# Flight_Controller.net
KiCad netlist of a schematic drawn in Altium Designer
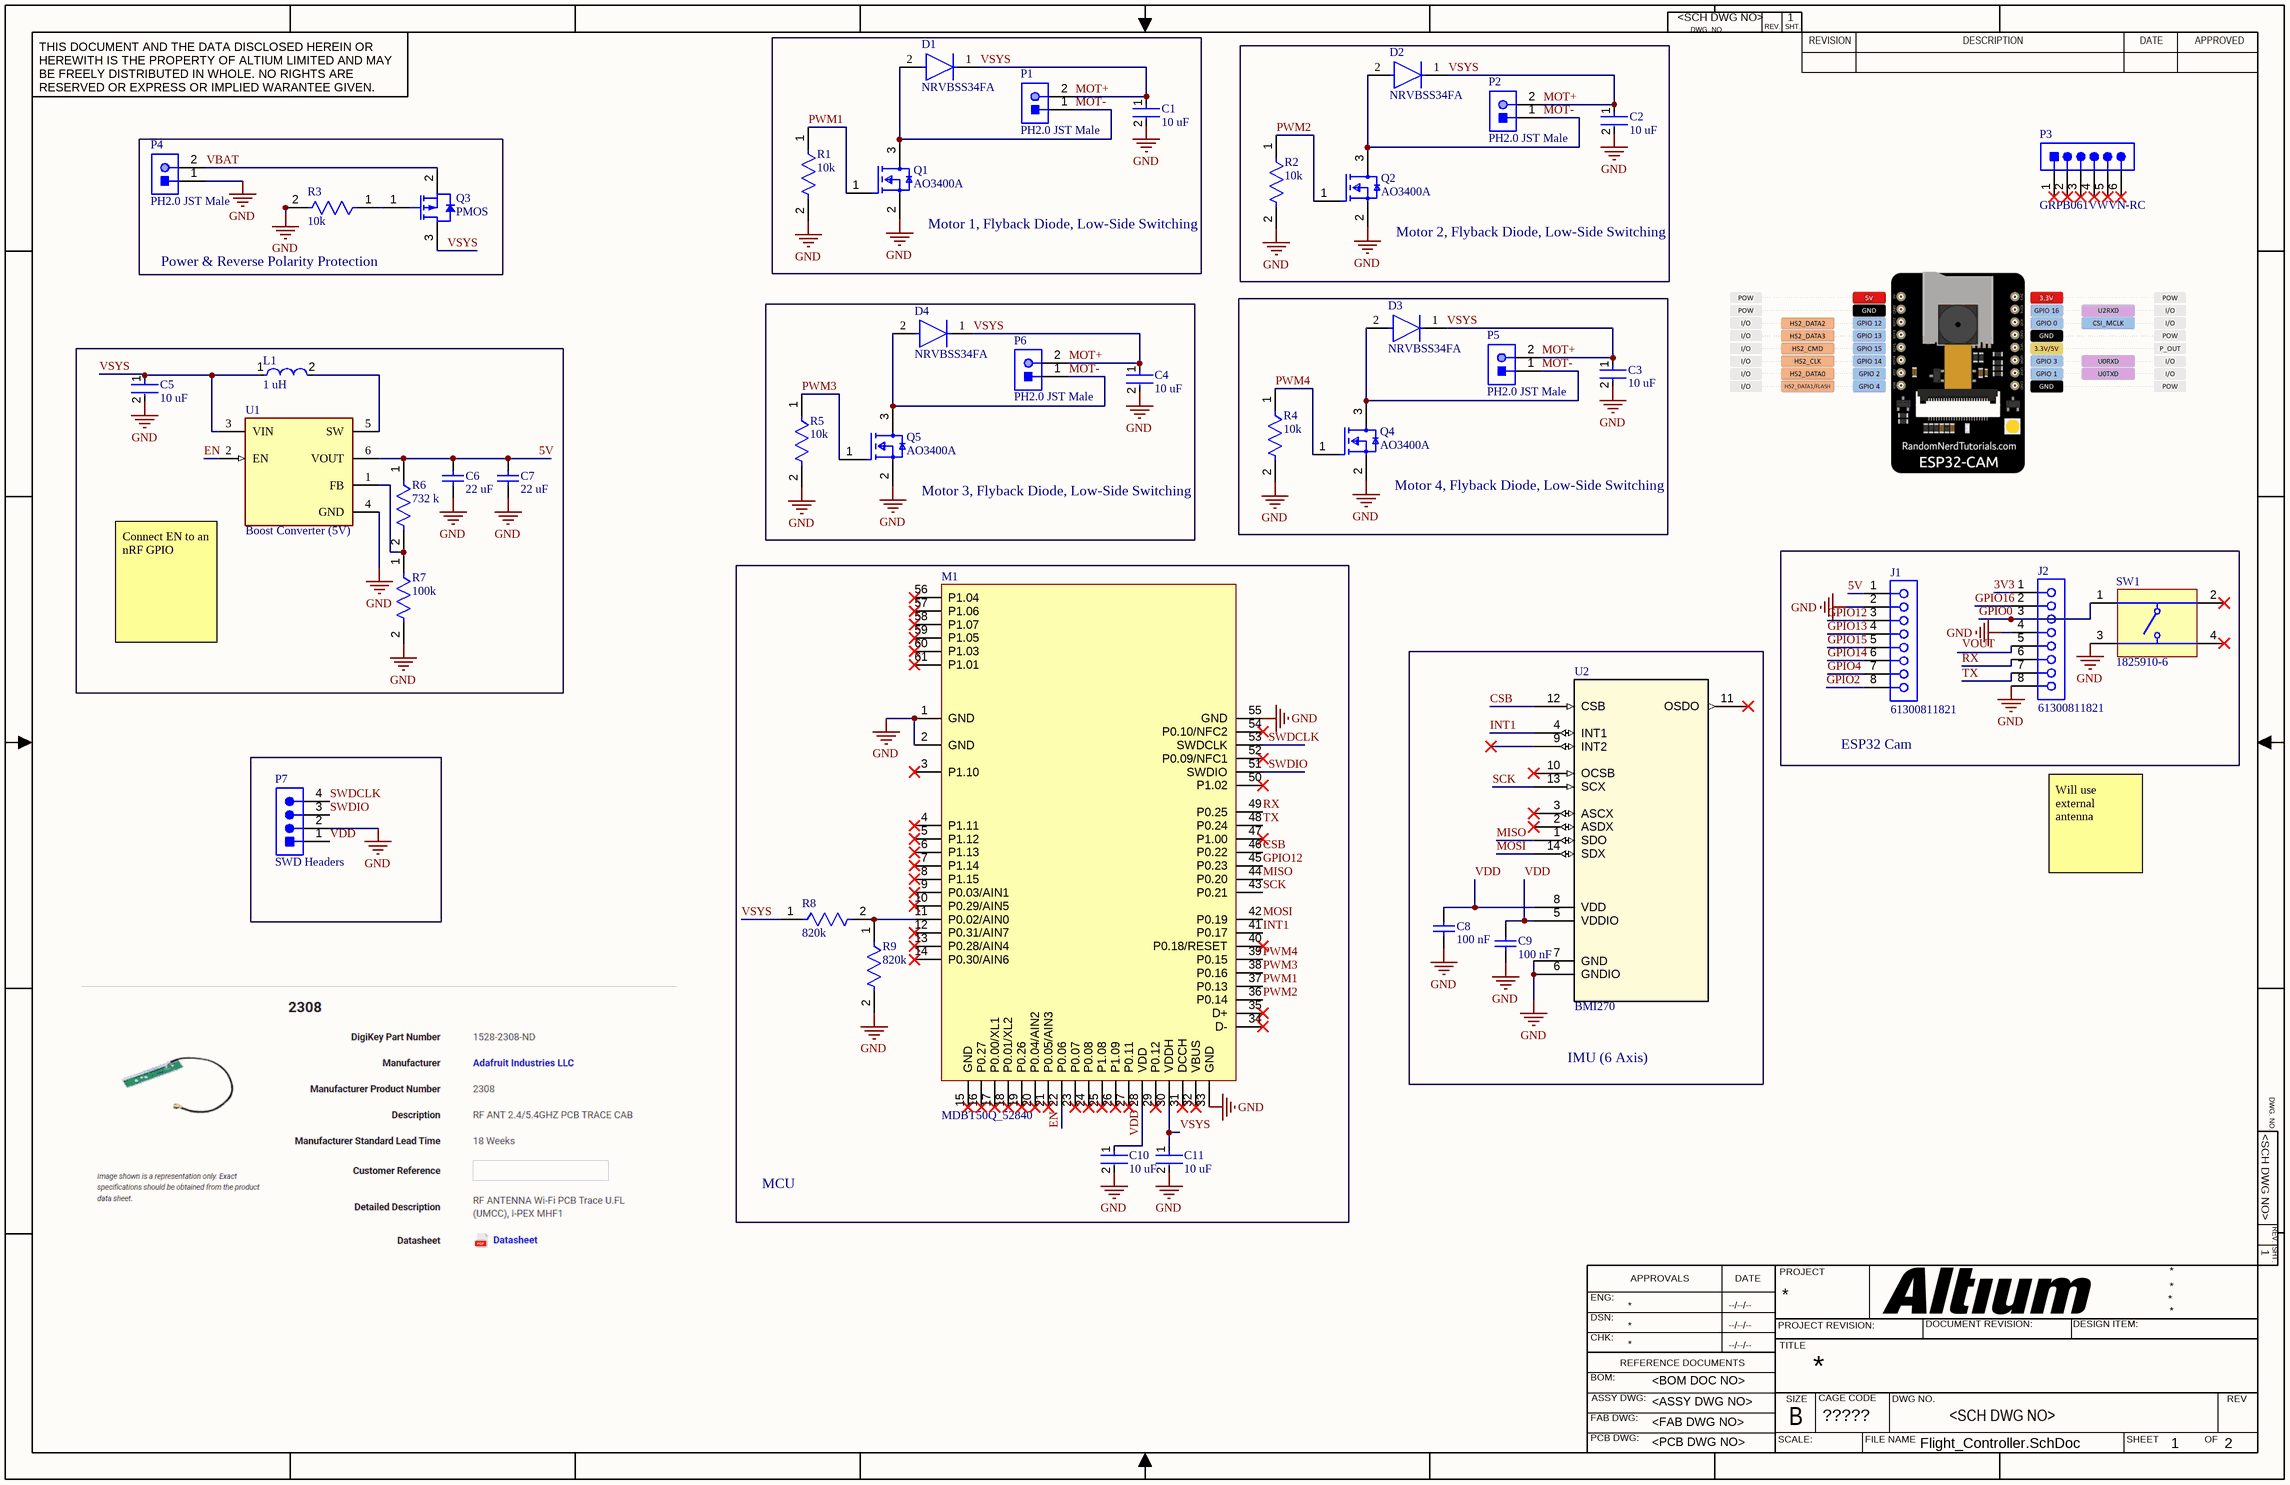
[diagram p0: Flight_Controller.SchDoc]

(export (version "E")
  (design (tool "Eeschema 10.0.6"))
  (components
    (comp (ref "C1")
      (value "10 uF")
      (footprint "FP-1210-L_3_3_0_4-W_2_5_0-IPC_A")
      (description "CAP CER 10UF 10V X7R 1210, 1210ZC106KAT2A")
      (fields (field (name "VOLTAGE") "10V") (field (name "TOLERANCE") "10%"))
      (libsource (lib "Altium Content Vault") (part "b4654b650e69147ec39a6b967a45e02"))
    )
    (comp (ref "C2")
      (value "10 uF")
      (footprint "FP-1210-L_3_3_0_4-W_2_5_0-IPC_A")
      (description "CAP CER 10UF 10V X7R 1210, 1210ZC106KAT2A")
      (fields (field (name "VOLTAGE") "10V") (field (name "TOLERANCE") "10%"))
      (libsource (lib "Altium Content Vault") (part "b4654b650e69147ec39a6b967a45e02"))
    )
    (comp (ref "C3")
      (value "10 uF")
      (footprint "FP-1210-L_3_3_0_4-W_2_5_0-IPC_A")
      (description "CAP CER 10UF 10V X7R 1210, 1210ZC106KAT2A")
      (fields (field (name "VOLTAGE") "10V") (field (name "TOLERANCE") "10%"))
      (libsource (lib "Altium Content Vault") (part "b4654b650e69147ec39a6b967a45e02"))
    )
    (comp (ref "C4")
      (value "10 uF")
      (footprint "FP-1210-L_3_3_0_4-W_2_5_0-IPC_A")
      (description "CAP CER 10UF 10V X7R 1210, 1210ZC106KAT2A")
      (fields (field (name "VOLTAGE") "10V") (field (name "TOLERANCE") "10%"))
      (libsource (lib "Altium Content Vault") (part "b4654b650e69147ec39a6b967a45e02"))
    )
    (comp (ref "C5")
      (value "10 uF")
      (footprint "FP-1210-L_3_3_0_4-W_2_5_0-IPC_A")
      (description "CAP CER 10UF 10V X7R 1210, 1210ZC106KAT2A")
      (fields (field (name "VOLTAGE") "10V") (field (name "TOLERANCE") "10%"))
      (libsource (lib "Altium Content Vault") (part "b4654b650e69147ec39a6b967a45e02"))
    )
    (comp (ref "C6")
      (value "22 uF")
      (footprint "CAPC1608X90X35ML15T15")
      (description "06034D226MAT2A")
      (fields (field (name "MANUFACTURER") "AVX Interconnect / Elco"))
      (libsource (lib "Altium Content Vault") (part "CAP"))
    )
    (comp (ref "C7")
      (value "22 uF")
      (footprint "CAPC1608X90X35ML15T15")
      (description "06034D226MAT2A")
      (fields (field (name "MANUFACTURER") "AVX Interconnect / Elco"))
      (libsource (lib "Altium Content Vault") (part "CAP"))
    )
    (comp (ref "C8")
      (value "100 nF")
      (footprint "CAPC1210(3225)100_L")
      (description "CAP 100nF 16V ±5% 1210 (3225 Metric) Thickness 1mm SMD")
      (fields (field (name "TOLERANCE") "Â±5%"))
      (libsource (lib "Altium Content Vault") (part "CAP"))
    )
    (comp (ref "C9")
      (value "100 nF")
      (footprint "CAPC1210(3225)100_L")
      (description "CAP 100nF 16V ±5% 1210 (3225 Metric) Thickness 1mm SMD")
      (fields (field (name "TOLERANCE") "Â±5%"))
      (libsource (lib "Altium Content Vault") (part "CAP"))
    )
    (comp (ref "C10")
      (value "10 uF")
      (footprint "FP-1210-L_3_3_0_4-W_2_5_0-IPC_A")
      (description "CAP CER 10UF 10V X7R 1210, 1210ZC106KAT2A")
      (fields (field (name "VOLTAGE") "10V") (field (name "TOLERANCE") "10%"))
      (libsource (lib "Altium Content Vault") (part "b4654b650e69147ec39a6b967a45e02"))
    )
    (comp (ref "C11")
      (value "10 uF")
      (footprint "FP-1210-L_3_3_0_4-W_2_5_0-IPC_A")
      (description "CAP CER 10UF 10V X7R 1210, 1210ZC106KAT2A")
      (fields (field (name "VOLTAGE") "10V") (field (name "TOLERANCE") "10%"))
      (libsource (lib "Altium Content Vault") (part "b4654b650e69147ec39a6b967a45e02"))
    )
    (comp (ref "D1")
      (value "NRVBSS34FA")
      (footprint "FP-425AB-MFG")
      (description "NRVBSS34FA Schottky Barrier Rectifier Diode 40V 3A 2-Pin SOD−123FL T/R")
      (libsource (lib "Altium Content Vault") (part "d7152d700b627762746794eb795d46e"))
    )
    (comp (ref "D2")
      (value "NRVBSS34FA")
      (footprint "FP-425AB-MFG")
      (description "NRVBSS34FA Schottky Barrier Rectifier Diode 40V 3A 2-Pin SOD−123FL T/R")
      (libsource (lib "Altium Content Vault") (part "d7152d700b627762746794eb795d46e"))
    )
    (comp (ref "D3")
      (value "NRVBSS34FA")
      (footprint "FP-425AB-MFG")
      (description "NRVBSS34FA Schottky Barrier Rectifier Diode 40V 3A 2-Pin SOD−123FL T/R")
      (libsource (lib "Altium Content Vault") (part "d7152d700b627762746794eb795d46e"))
    )
    (comp (ref "D4")
      (value "NRVBSS34FA")
      (footprint "FP-425AB-MFG")
      (description "NRVBSS34FA Schottky Barrier Rectifier Diode 40V 3A 2-Pin SOD−123FL T/R")
      (libsource (lib "Altium Content Vault") (part "d7152d700b627762746794eb795d46e"))
    )
    (comp (ref "J1")
      (value "61300811821")
      (footprint "61300811821")
      (description "Btb Conn, Rcpt, 8Pos, 1Row, 2.54Mm Rohs Compliant: Yes")
      (libsource (lib "Altium Content Vault") (part "Header_Female_1R_08P"))
    )
    (comp (ref "J2")
      (value "61300811821")
      (footprint "61300811821")
      (description "Btb Conn, Rcpt, 8Pos, 1Row, 2.54Mm Rohs Compliant: Yes")
      (libsource (lib "Altium Content Vault") (part "Header_Female_1R_08P"))
    )
    (comp (ref "L1")
      (value "1 uH")
      (footprint "FP-MLP2016M-IPC_C")
      (description "Shielded Multilayer Inductor 1uH ±20% 1400mA 117mΩ SMD 0806, MLP2016S1R0MT0S1")
      (fields (field (name "TOLERANCE") "20%"))
      (libsource (lib "Altium Content Vault") (part "725321dda6339637d4d059423bc1c3c"))
    )
    (comp (ref "M1")
      (value "MDBT50Q_52840")
      (footprint "MDBT50Q")
      (description "MDBT50Q(52840)")
      (libsource (lib "MDBT50Q_52840_230606") (part "MDBT50Q_52840"))
    )
    (comp (ref "P1")
      (value "PH2.0 JST Male")
      (footprint "JST-S2B-PH-K-S_V")
      (fields (field (name "MANUFACTURER") "Japan Solderless Terminals"))
      (libsource (lib "Altium 365 Cloud") (part "CN-1P-M-R2"))
    )
    (comp (ref "P2")
      (value "PH2.0 JST Male")
      (footprint "JST-S2B-PH-K-S_V")
      (fields (field (name "MANUFACTURER") "Japan Solderless Terminals"))
      (libsource (lib "Altium 365 Cloud") (part "CN-1P-M-R2"))
    )
    (comp (ref "P3")
      (value "GRPB061VWVN-RC")
      (footprint "SLIN-GRPB061VWVN-RC_V")
      (fields (field (name "MANUFACTURER") "Sullins"))
      (libsource (lib "Altium Content Vault") (part "CN-1P-M-R6"))
    )
    (comp (ref "P4")
      (value "PH2.0 JST Male")
      (footprint "JST-S2B-PH-K-S_V")
      (fields (field (name "MANUFACTURER") "Japan Solderless Terminals"))
      (libsource (lib "Altium 365 Cloud") (part "CN-1P-M-R2"))
    )
    (comp (ref "P5")
      (value "PH2.0 JST Male")
      (footprint "JST-S2B-PH-K-S_V")
      (fields (field (name "MANUFACTURER") "Japan Solderless Terminals"))
      (libsource (lib "Altium 365 Cloud") (part "CN-1P-M-R2"))
    )
    (comp (ref "P6")
      (value "PH2.0 JST Male")
      (footprint "JST-S2B-PH-K-S_V")
      (fields (field (name "MANUFACTURER") "Japan Solderless Terminals"))
      (libsource (lib "Altium 365 Cloud") (part "CN-1P-M-R2"))
    )
    (comp (ref "P7")
      (value "SWD Headers")
      (footprint "SLIN-GRPB041VWVN-RC_V")
      (fields (field (name "MANUFACTURER") "Sullins"))
      (libsource (lib "Altium Content Vault") (part "CN-1P-M-R4"))
    )
    (comp (ref "Q1")
      (value "AO3400A")
      (footprint "FP-SOT23-MFG")
      (description "MOSFET N-CH 30V 5.7A SOT23")
      (libsource (lib "Altium Content Vault") (part "0a9ea7c96deaaede766a5b531c28de0"))
    )
    (comp (ref "Q2")
      (value "AO3400A")
      (footprint "FP-SOT23-MFG")
      (description "MOSFET N-CH 30V 5.7A SOT23")
      (libsource (lib "Altium Content Vault") (part "0a9ea7c96deaaede766a5b531c28de0"))
    )
    (comp (ref "Q3")
      (value "PMOS")
      (footprint "AO-SOT-23-3L_V")
      (description "P-Channel MOSFET, 30 V, 4 A, -55 to 150 degC, 3-Pin SOT-23-3L, RoHS, Tape and Reel, AO3401A")
      (fields (field (name "MANUFACTURER") "Alpha and Omega"))
      (libsource (lib "Altium Content Vault") (part "PEMOS-GSD-3"))
    )
    (comp (ref "Q4")
      (value "AO3400A")
      (footprint "FP-SOT23-MFG")
      (description "MOSFET N-CH 30V 5.7A SOT23")
      (libsource (lib "Altium Content Vault") (part "0a9ea7c96deaaede766a5b531c28de0"))
    )
    (comp (ref "Q5")
      (value "AO3400A")
      (footprint "FP-SOT23-MFG")
      (description "MOSFET N-CH 30V 5.7A SOT23")
      (libsource (lib "Altium Content Vault") (part "0a9ea7c96deaaede766a5b531c28de0"))
    )
    (comp (ref "R1")
      (value "10k")
      (footprint "FP-CRGCQ1210-IPC_C")
      (description "CRGCQ1210 10KΩ 0.5W ±100ppm/°C 5% 200V")
      (fields (field (name "TOLERANCE") "0.05") (field (name "MANUFACTURER PART NUMBER") "CRGCQ1210J10K"))
      (libsource (lib "Altium Content Vault") (part "1029c3af85768c4190bb7ad29bc67b5"))
    )
    (comp (ref "R2")
      (value "10k")
      (footprint "FP-CRGCQ1210-IPC_C")
      (description "CRGCQ1210 10KΩ 0.5W ±100ppm/°C 5% 200V")
      (fields (field (name "TOLERANCE") "0.05") (field (name "MANUFACTURER PART NUMBER") "CRGCQ1210J10K"))
      (libsource (lib "Altium Content Vault") (part "1029c3af85768c4190bb7ad29bc67b5"))
    )
    (comp (ref "R3")
      (value "10k")
      (footprint "FP-CRGCQ1210-IPC_C")
      (description "CRGCQ1210 10KΩ 0.5W ±100ppm/°C 5% 200V")
      (fields (field (name "TOLERANCE") "0.05") (field (name "MANUFACTURER PART NUMBER") "CRGCQ1210J10K"))
      (libsource (lib "Altium Content Vault") (part "1029c3af85768c4190bb7ad29bc67b5"))
    )
    (comp (ref "R4")
      (value "10k")
      (footprint "FP-CRGCQ1210-IPC_C")
      (description "CRGCQ1210 10KΩ 0.5W ±100ppm/°C 5% 200V")
      (fields (field (name "TOLERANCE") "0.05") (field (name "MANUFACTURER PART NUMBER") "CRGCQ1210J10K"))
      (libsource (lib "Altium Content Vault") (part "1029c3af85768c4190bb7ad29bc67b5"))
    )
    (comp (ref "R5")
      (value "10k")
      (footprint "FP-CRGCQ1210-IPC_C")
      (description "CRGCQ1210 10KΩ 0.5W ±100ppm/°C 5% 200V")
      (fields (field (name "TOLERANCE") "0.05") (field (name "MANUFACTURER PART NUMBER") "CRGCQ1210J10K"))
      (libsource (lib "Altium Content Vault") (part "1029c3af85768c4190bb7ad29bc67b5"))
    )
    (comp (ref "R6")
      (value "732 k")
      (footprint "FP-AC0603-IPC_B")
      (description "RES 732KΩ 1.00% 0.1W 0603, AC0603FR-07732KL")
      (fields (field (name "TOLERANCE") "1%"))
      (libsource (lib "Altium Content Vault") (part "1029c3af85768c4190bb7ad29bc67b5"))
    )
    (comp (ref "R7")
      (value "100k")
      (footprint "FP-AC1210-MFG")
      (description "RES SMD 100K OHM 5% 1/2W 1210, AC1210JR-07100KL")
      (fields
        (field (name "MANUFACTURER") "Yageo")
        (field (name "MANUFACTURER PART NUMBER") "AC1210JR-07100KL")
      )
      (libsource (lib "Altium Content Vault") (part "1029c3af85768c4190bb7ad29bc67b5"))
    )
    (comp (ref "R8")
      (value "820k")
      (footprint "FP-AC1206-MFG")
      (description "RES SMD 820K OHM 1% 1/4W 1206, AC1206FR-07820KL")
      (fields
        (field (name "TOLERANCE") "0.01")
        (field (name "OCTOPART") "https://octopart.com/ac1206fr-07820kl-yageo-71368214")
      )
      (libsource (lib "Altium Content Vault") (part "1029c3af85768c4190bb7ad29bc67b5"))
    )
    (comp (ref "R9")
      (value "820k")
      (footprint "FP-AC1206-MFG")
      (description "RES SMD 820K OHM 1% 1/4W 1206, AC1206FR-07820KL")
      (fields
        (field (name "TOLERANCE") "0.01")
        (field (name "OCTOPART") "https://octopart.com/ac1206fr-07820kl-yageo-71368214")
      )
      (libsource (lib "Altium Content Vault") (part "1029c3af85768c4190bb7ad29bc67b5"))
    )
    (comp (ref "SW1")
      (value "1825910-6")
      (footprint "TECO-1825910-6_V")
      (description "Tact Switch, SPST-NO, 0.05 A, -35 to 85 degC, 4-Pin THD, RoHS, Bulk")
      (fields (field (name "MANUFACTURER") "TE Connectivity"))
      (libsource (lib "Altium Content Vault") (part "SW-SPST-4_A"))
    )
    (comp (ref "U1")
      (value "Boost Converter (5V)")
      (footprint "FP-DRL0006A-MFG")
      (description "FINISH GOODS FOR TPS61023,TPS61023DRLR")
      (libsource (lib "Altium Content Vault") (part "b28b3e956a4ad07201ce69f9d09f9a8"))
    )
    (comp (ref "U2")
      (value "BMI270")
      (footprint "BMI270_BOS")
      (description "Description")
      (fields (field (name "COPYRIGHT") "Copyright (C) 2025 Ultra Librarian. All rights reserved."))
      (libsource (lib "BMI270") (part "BMI270"))
    )
  )
  (nets
    (net (code "1") (name "/3V3") (class "Default")
      (node (ref "J2") (pin "1") (pinfunction "1_1") (pintype "passive"))
    )
    (net (code "2") (name "/5V") (class "Default")
      (node (ref "C6") (pin "1") (pinfunction "1_1") (pintype "passive"))
      (node (ref "C7") (pin "1") (pinfunction "1_1") (pintype "passive"))
      (node (ref "J1") (pin "1") (pinfunction "1_1") (pintype "passive"))
      (node (ref "R6") (pin "1") (pinfunction "1_1") (pintype "passive"))
      (node (ref "U1") (pin "6") (pinfunction "VOUT_6") (pintype "power_in"))
    )
    (net (code "3") (name "/CSB") (class "Default")
      (node (ref "M1") (pin "46") (pinfunction "P0.22_46") (pintype "passive"))
      (node (ref "U2") (pin "12") (pinfunction "CSB_12") (pintype "input"))
    )
    (net (code "4") (name "/EN") (class "Default")
      (node (ref "M1") (pin "22") (pinfunction "P0.06_22") (pintype "passive"))
      (node (ref "U1") (pin "2") (pinfunction "EN_2") (pintype "input"))
    )
    (net (code "5") (name "/GPIO0") (class "Default")
      (node (ref "J2") (pin "3") (pinfunction "3_3") (pintype "passive"))
      (node (ref "SW1") (pin "1") (pinfunction "1_1") (pintype "passive"))
    )
    (net (code "6") (name "/GPIO2") (class "Default")
      (node (ref "J1") (pin "8") (pinfunction "8_8") (pintype "passive"))
    )
    (net (code "7") (name "/GPIO4") (class "Default")
      (node (ref "J1") (pin "7") (pinfunction "7_7") (pintype "passive"))
    )
    (net (code "8") (name "/GPIO12") (class "Default")
      (node (ref "J1") (pin "3") (pinfunction "3_3") (pintype "passive"))
      (node (ref "M1") (pin "45") (pinfunction "P0.23_45") (pintype "passive"))
    )
    (net (code "9") (name "/GPIO13") (class "Default")
      (node (ref "J1") (pin "4") (pinfunction "4_4") (pintype "passive"))
    )
    (net (code "10") (name "/GPIO14") (class "Default")
      (node (ref "J1") (pin "6") (pinfunction "6_6") (pintype "passive"))
    )
    (net (code "11") (name "/GPIO15") (class "Default")
      (node (ref "J1") (pin "5") (pinfunction "5_5") (pintype "passive"))
    )
    (net (code "12") (name "/GPIO16") (class "Default")
      (node (ref "J2") (pin "2") (pinfunction "2_2") (pintype "passive"))
    )
    (net (code "13") (name "/INT1") (class "Default")
      (node (ref "M1") (pin "41") (pinfunction "P0.17_41") (pintype "passive"))
      (node (ref "U2") (pin "4") (pinfunction "INT1_4") (pintype "bidirectional"))
    )
    (net (code "14") (name "/MISO") (class "Default")
      (node (ref "M1") (pin "44") (pinfunction "P0.20_44") (pintype "passive"))
      (node (ref "U2") (pin "1") (pinfunction "SDO_1") (pintype "bidirectional"))
    )
    (net (code "15") (name "/MOSI") (class "Default")
      (node (ref "M1") (pin "42") (pinfunction "P0.19_42") (pintype "passive"))
      (node (ref "U2") (pin "14") (pinfunction "SDX_14") (pintype "bidirectional"))
    )
    (net (code "16") (name "/MOT+") (class "Default")
      (node (ref "C1") (pin "1") (pinfunction "1_1") (pintype "passive"))
      (node (ref "C11") (pin "1") (pinfunction "1_1") (pintype "passive"))
      (node (ref "C2") (pin "1") (pinfunction "1_1") (pintype "passive"))
      (node (ref "C3") (pin "1") (pinfunction "1_1") (pintype "passive"))
      (node (ref "C4") (pin "1") (pinfunction "1_1") (pintype "passive"))
      (node (ref "C5") (pin "1") (pinfunction "1_1") (pintype "passive"))
      (node (ref "D1") (pin "1") (pinfunction "C_1") (pintype "passive"))
      (node (ref "D2") (pin "1") (pinfunction "C_1") (pintype "passive"))
      (node (ref "D3") (pin "1") (pinfunction "C_1") (pintype "passive"))
      (node (ref "D4") (pin "1") (pinfunction "C_1") (pintype "passive"))
      (node (ref "L1") (pin "1") (pinfunction "1_1") (pintype "passive"))
      (node (ref "M1") (pin "30") (pinfunction "VDDH_30") (pintype "passive"))
      (node (ref "P1") (pin "2") (pinfunction "2_2") (pintype "passive"))
      (node (ref "P2") (pin "2") (pinfunction "2_2") (pintype "passive"))
      (node (ref "P5") (pin "2") (pinfunction "2_2") (pintype "passive"))
      (node (ref "P6") (pin "2") (pinfunction "2_2") (pintype "passive"))
      (node (ref "Q3") (pin "3") (pinfunction "DRAIN_3") (pintype "passive"))
      (node (ref "R8") (pin "1") (pinfunction "1_1") (pintype "passive"))
      (node (ref "U1") (pin "3") (pinfunction "VIN_3") (pintype "power_in"))
    )
    (net (code "17") (name "/MOT-") (class "Default")
      (node (ref "D1") (pin "2") (pinfunction "A_2") (pintype "passive"))
      (node (ref "D2") (pin "2") (pinfunction "A_2") (pintype "passive"))
      (node (ref "D3") (pin "2") (pinfunction "A_2") (pintype "passive"))
      (node (ref "D4") (pin "2") (pinfunction "A_2") (pintype "passive"))
      (node (ref "P1") (pin "1") (pinfunction "1_1") (pintype "passive"))
      (node (ref "P2") (pin "1") (pinfunction "1_1") (pintype "passive"))
      (node (ref "P5") (pin "1") (pinfunction "1_1") (pintype "passive"))
      (node (ref "P6") (pin "1") (pinfunction "1_1") (pintype "passive"))
      (node (ref "Q1") (pin "3") (pinfunction "D_3") (pintype "passive"))
      (node (ref "Q2") (pin "3") (pinfunction "D_3") (pintype "passive"))
      (node (ref "Q4") (pin "3") (pinfunction "D_3") (pintype "passive"))
      (node (ref "Q5") (pin "3") (pinfunction "D_3") (pintype "passive"))
    )
    (net (code "18") (name "/PWM1") (class "Default")
      (node (ref "M1") (pin "37") (pinfunction "P0.13_37") (pintype "passive"))
      (node (ref "Q1") (pin "1") (pinfunction "G_1") (pintype "passive"))
      (node (ref "R1") (pin "1") (pinfunction "1_1") (pintype "passive"))
    )
    (net (code "19") (name "/PWM2") (class "Default")
      (node (ref "M1") (pin "36") (pinfunction "P0.14_36") (pintype "passive"))
      (node (ref "Q2") (pin "1") (pinfunction "G_1") (pintype "passive"))
      (node (ref "R2") (pin "1") (pinfunction "1_1") (pintype "passive"))
    )
    (net (code "20") (name "/PWM3") (class "Default")
      (node (ref "M1") (pin "38") (pinfunction "P0.16_38") (pintype "passive"))
      (node (ref "Q5") (pin "1") (pinfunction "G_1") (pintype "passive"))
      (node (ref "R5") (pin "1") (pinfunction "1_1") (pintype "passive"))
    )
    (net (code "21") (name "/PWM4") (class "Default")
      (node (ref "M1") (pin "39") (pinfunction "P0.15_39") (pintype "passive"))
      (node (ref "Q4") (pin "1") (pinfunction "G_1") (pintype "passive"))
      (node (ref "R4") (pin "1") (pinfunction "1_1") (pintype "passive"))
    )
    (net (code "22") (name "/RX") (class "Default")
      (node (ref "J2") (pin "6") (pinfunction "6_6") (pintype "passive"))
      (node (ref "M1") (pin "49") (pinfunction "P0.25_49") (pintype "passive"))
    )
    (net (code "23") (name "/SCK") (class "Default")
      (node (ref "M1") (pin "43") (pinfunction "P0.21_43") (pintype "passive"))
      (node (ref "U2") (pin "13") (pinfunction "SCX_13") (pintype "input"))
    )
    (net (code "24") (name "/SWDCLK") (class "Default")
      (node (ref "M1") (pin "53") (pinfunction "SWDCLK_53") (pintype "passive"))
      (node (ref "P7") (pin "4") (pinfunction "4_4") (pintype "passive"))
    )
    (net (code "25") (name "/SWDIO") (class "Default")
      (node (ref "M1") (pin "51") (pinfunction "SWDIO_51") (pintype "passive"))
      (node (ref "P7") (pin "3") (pinfunction "3_3") (pintype "passive"))
    )
    (net (code "26") (name "/TX") (class "Default")
      (node (ref "J2") (pin "7") (pinfunction "7_7") (pintype "passive"))
      (node (ref "M1") (pin "48") (pinfunction "P0.24_48") (pintype "passive"))
    )
    (net (code "27") (name "/VBAT") (class "Default")
      (node (ref "P4") (pin "2") (pinfunction "2_2") (pintype "passive"))
      (node (ref "Q3") (pin "2") (pinfunction "SOURCE_2") (pintype "passive"))
    )
    (net (code "28") (name "/VDD") (class "Default")
      (node (ref "C10") (pin "1") (pinfunction "1_1") (pintype "passive"))
      (node (ref "C8") (pin "2") (pinfunction "2_2") (pintype "passive"))
      (node (ref "C9") (pin "2") (pinfunction "2_2") (pintype "passive"))
      (node (ref "M1") (pin "28") (pinfunction "VDD_28") (pintype "passive"))
      (node (ref "P7") (pin "1") (pinfunction "1_1") (pintype "passive"))
      (node (ref "U2") (pin "5") (pinfunction "VDDIO_5") (pintype "power_in"))
      (node (ref "U2") (pin "8") (pinfunction "VDD_8") (pintype "power_in"))
    )
    (net (code "30") (name "GND") (class "Default")
      (node (ref "C1") (pin "2") (pinfunction "2_2") (pintype "passive"))
      (node (ref "C10") (pin "2") (pinfunction "2_2") (pintype "passive"))
      (node (ref "C11") (pin "2") (pinfunction "2_2") (pintype "passive"))
      (node (ref "C2") (pin "2") (pinfunction "2_2") (pintype "passive"))
      (node (ref "C3") (pin "2") (pinfunction "2_2") (pintype "passive"))
      (node (ref "C4") (pin "2") (pinfunction "2_2") (pintype "passive"))
      (node (ref "C5") (pin "2") (pinfunction "2_2") (pintype "passive"))
      (node (ref "C6") (pin "2") (pinfunction "2_2") (pintype "passive"))
      (node (ref "C7") (pin "2") (pinfunction "2_2") (pintype "passive"))
      (node (ref "C8") (pin "1") (pinfunction "1_1") (pintype "passive"))
      (node (ref "C9") (pin "1") (pinfunction "1_1") (pintype "passive"))
      (node (ref "J1") (pin "2") (pinfunction "2_2") (pintype "passive"))
      (node (ref "J2") (pin "4") (pinfunction "4_4") (pintype "passive"))
      (node (ref "J2") (pin "8") (pinfunction "8_8") (pintype "passive"))
      (node (ref "M1") (pin "1") (pinfunction "GND_1") (pintype "passive"))
      (node (ref "M1") (pin "2") (pinfunction "GND_2") (pintype "passive"))
      (node (ref "M1") (pin "33") (pinfunction "GND_33") (pintype "passive"))
      (node (ref "M1") (pin "55") (pinfunction "GND_55") (pintype "passive"))
      (node (ref "P4") (pin "1") (pinfunction "1_1") (pintype "passive"))
      (node (ref "P7") (pin "2") (pinfunction "2_2") (pintype "passive"))
      (node (ref "Q1") (pin "2") (pinfunction "S_2") (pintype "passive"))
      (node (ref "Q2") (pin "2") (pinfunction "S_2") (pintype "passive"))
      (node (ref "Q4") (pin "2") (pinfunction "S_2") (pintype "passive"))
      (node (ref "Q5") (pin "2") (pinfunction "S_2") (pintype "passive"))
      (node (ref "R1") (pin "2") (pinfunction "2_2") (pintype "passive"))
      (node (ref "R2") (pin "2") (pinfunction "2_2") (pintype "passive"))
      (node (ref "R3") (pin "2") (pinfunction "2_2") (pintype "passive"))
      (node (ref "R4") (pin "2") (pinfunction "2_2") (pintype "passive"))
      (node (ref "R5") (pin "2") (pinfunction "2_2") (pintype "passive"))
      (node (ref "R7") (pin "2") (pinfunction "2_2") (pintype "passive"))
      (node (ref "R9") (pin "2") (pinfunction "2_2") (pintype "passive"))
      (node (ref "SW1") (pin "3") (pinfunction "3_3") (pintype "passive"))
      (node (ref "U1") (pin "4") (pinfunction "GND_4") (pintype "power_in"))
      (node (ref "U2") (pin "6") (pinfunction "GNDIO_6") (pintype "power_in"))
      (node (ref "U2") (pin "7") (pinfunction "GND_7") (pintype "power_in"))
    )
    (net (code "31") (name "Net-(M1-P0.02{slash}AIN0)") (class "Default")
      (node (ref "M1") (pin "11") (pinfunction "P0.02/AIN0_11") (pintype "passive"))
      (node (ref "R8") (pin "2") (pinfunction "2_2") (pintype "passive"))
      (node (ref "R9") (pin "1") (pinfunction "1_1") (pintype "passive"))
    )
    (net (code "32") (name "Net-(Q3-GATE)") (class "Default")
      (node (ref "Q3") (pin "1") (pinfunction "GATE_1") (pintype "passive"))
      (node (ref "R3") (pin "1") (pinfunction "1_1") (pintype "passive"))
    )
    (net (code "33") (name "Net-(U1-FB)") (class "Default")
      (node (ref "R6") (pin "2") (pinfunction "2_2") (pintype "passive"))
      (node (ref "R7") (pin "1") (pinfunction "1_1") (pintype "passive"))
      (node (ref "U1") (pin "1") (pinfunction "FB_1") (pintype "passive"))
    )
    (net (code "34") (name "Net-(U1-SW)") (class "Default")
      (node (ref "L1") (pin "2") (pinfunction "2_2") (pintype "passive"))
      (node (ref "U1") (pin "5") (pinfunction "SW_5") (pintype "passive"))
    )
    (net (code "35") (name "unconnected-(J2-Pad5)") (class "Default")
      (node (ref "J2") (pin "5") (pinfunction "5_5") (pintype "passive"))
    )
    (net (code "36") (name "unconnected-(M1-D+-Pad35)") (class "Default")
      (node (ref "M1") (pin "35") (pinfunction "D+_35") (pintype "passive+no_connect"))
    )
    (net (code "37") (name "unconnected-(M1-D--Pad34)") (class "Default")
      (node (ref "M1") (pin "34") (pinfunction "D-_34") (pintype "passive+no_connect"))
    )
    (net (code "38") (name "unconnected-(M1-DCCH-Pad31)") (class "Default")
      (node (ref "M1") (pin "31") (pinfunction "DCCH_31") (pintype "passive+no_connect"))
    )
    (net (code "39") (name "unconnected-(M1-GND-Pad15)") (class "Default")
      (node (ref "M1") (pin "15") (pinfunction "GND_15") (pintype "passive+no_connect"))
    )
    (net (code "40") (name "unconnected-(M1-P0.00{slash}XL1-Pad17)") (class "Default")
      (node (ref "M1") (pin "17") (pinfunction "P0.00/XL1_17") (pintype "passive+no_connect"))
    )
    (net (code "41") (name "unconnected-(M1-P0.01{slash}XL2-Pad18)") (class "Default")
      (node (ref "M1") (pin "18") (pinfunction "P0.01/XL2_18") (pintype "passive+no_connect"))
    )
    (net (code "42") (name "unconnected-(M1-P0.03{slash}AIN1-Pad9)") (class "Default")
      (node (ref "M1") (pin "9") (pinfunction "P0.03/AIN1_9") (pintype "passive+no_connect"))
    )
    (net (code "43") (name "unconnected-(M1-P0.04{slash}AIN2-Pad20)") (class "Default")
      (node (ref "M1") (pin "20") (pinfunction "P0.04/AIN2_20") (pintype "passive+no_connect"))
    )
    (net (code "44") (name "unconnected-(M1-P0.05{slash}AIN3-Pad21)") (class "Default")
      (node (ref "M1") (pin "21") (pinfunction "P0.05/AIN3_21") (pintype "passive+no_connect"))
    )
    (net (code "45") (name "unconnected-(M1-P0.07-Pad23)") (class "Default")
      (node (ref "M1") (pin "23") (pinfunction "P0.07_23") (pintype "passive+no_connect"))
    )
    (net (code "46") (name "unconnected-(M1-P0.08-Pad24)") (class "Default")
      (node (ref "M1") (pin "24") (pinfunction "P0.08_24") (pintype "passive+no_connect"))
    )
    (net (code "47") (name "unconnected-(M1-P0.09{slash}NFC1-Pad52)") (class "Default")
      (node (ref "M1") (pin "52") (pinfunction "P0.09/NFC1_52") (pintype "passive+no_connect"))
    )
    (net (code "48") (name "unconnected-(M1-P0.10{slash}NFC2-Pad54)") (class "Default")
      (node (ref "M1") (pin "54") (pinfunction "P0.10/NFC2_54") (pintype "passive+no_connect"))
    )
    (net (code "49") (name "unconnected-(M1-P0.11-Pad27)") (class "Default")
      (node (ref "M1") (pin "27") (pinfunction "P0.11_27") (pintype "passive+no_connect"))
    )
    (net (code "50") (name "unconnected-(M1-P0.12-Pad29)") (class "Default")
      (node (ref "M1") (pin "29") (pinfunction "P0.12_29") (pintype "passive+no_connect"))
    )
    (net (code "51") (name "unconnected-(M1-P0.18{slash}RESET-Pad40)") (class "Default")
      (node (ref "M1") (pin "40") (pinfunction "P0.18/RESET_40") (pintype "passive+no_connect"))
    )
    (net (code "52") (name "unconnected-(M1-P0.26-Pad19)") (class "Default")
      (node (ref "M1") (pin "19") (pinfunction "P0.26_19") (pintype "passive+no_connect"))
    )
    (net (code "53") (name "unconnected-(M1-P0.27-Pad16)") (class "Default")
      (node (ref "M1") (pin "16") (pinfunction "P0.27_16") (pintype "passive+no_connect"))
    )
    (net (code "54") (name "unconnected-(M1-P0.28{slash}AIN4-Pad13)") (class "Default")
      (node (ref "M1") (pin "13") (pinfunction "P0.28/AIN4_13") (pintype "passive+no_connect"))
    )
    (net (code "55") (name "unconnected-(M1-P0.29{slash}AIN5-Pad10)") (class "Default")
      (node (ref "M1") (pin "10") (pinfunction "P0.29/AIN5_10") (pintype "passive+no_connect"))
    )
    (net (code "56") (name "unconnected-(M1-P0.30{slash}AIN6-Pad14)") (class "Default")
      (node (ref "M1") (pin "14") (pinfunction "P0.30/AIN6_14") (pintype "passive+no_connect"))
    )
    (net (code "57") (name "unconnected-(M1-P0.31{slash}AIN7-Pad12)") (class "Default")
      (node (ref "M1") (pin "12") (pinfunction "P0.31/AIN7_12") (pintype "passive+no_connect"))
    )
    (net (code "58") (name "unconnected-(M1-P1.00-Pad47)") (class "Default")
      (node (ref "M1") (pin "47") (pinfunction "P1.00_47") (pintype "passive+no_connect"))
    )
    (net (code "59") (name "unconnected-(M1-P1.01-Pad61)") (class "Default")
      (node (ref "M1") (pin "61") (pinfunction "P1.01_61") (pintype "passive+no_connect"))
    )
    (net (code "60") (name "unconnected-(M1-P1.02-Pad50)") (class "Default")
      (node (ref "M1") (pin "50") (pinfunction "P1.02_50") (pintype "passive+no_connect"))
    )
    (net (code "61") (name "unconnected-(M1-P1.03-Pad60)") (class "Default")
      (node (ref "M1") (pin "60") (pinfunction "P1.03_60") (pintype "passive+no_connect"))
    )
    (net (code "62") (name "unconnected-(M1-P1.04-Pad56)") (class "Default")
      (node (ref "M1") (pin "56") (pinfunction "P1.04_56") (pintype "passive+no_connect"))
    )
    (net (code "63") (name "unconnected-(M1-P1.05-Pad59)") (class "Default")
      (node (ref "M1") (pin "59") (pinfunction "P1.05_59") (pintype "passive+no_connect"))
    )
    (net (code "64") (name "unconnected-(M1-P1.06-Pad57)") (class "Default")
      (node (ref "M1") (pin "57") (pinfunction "P1.06_57") (pintype "passive+no_connect"))
    )
    (net (code "65") (name "unconnected-(M1-P1.07-Pad58)") (class "Default")
      (node (ref "M1") (pin "58") (pinfunction "P1.07_58") (pintype "passive+no_connect"))
    )
    (net (code "66") (name "unconnected-(M1-P1.08-Pad25)") (class "Default")
      (node (ref "M1") (pin "25") (pinfunction "P1.08_25") (pintype "passive+no_connect"))
    )
    (net (code "67") (name "unconnected-(M1-P1.09-Pad26)") (class "Default")
      (node (ref "M1") (pin "26") (pinfunction "P1.09_26") (pintype "passive+no_connect"))
    )
    (net (code "68") (name "unconnected-(M1-P1.10-Pad3)") (class "Default")
      (node (ref "M1") (pin "3") (pinfunction "P1.10_3") (pintype "passive+no_connect"))
    )
    (net (code "69") (name "unconnected-(M1-P1.11-Pad4)") (class "Default")
      (node (ref "M1") (pin "4") (pinfunction "P1.11_4") (pintype "passive+no_connect"))
    )
    (net (code "70") (name "unconnected-(M1-P1.12-Pad5)") (class "Default")
      (node (ref "M1") (pin "5") (pinfunction "P1.12_5") (pintype "passive+no_connect"))
    )
    (net (code "71") (name "unconnected-(M1-P1.13-Pad6)") (class "Default")
      (node (ref "M1") (pin "6") (pinfunction "P1.13_6") (pintype "passive+no_connect"))
    )
    (net (code "72") (name "unconnected-(M1-P1.14-Pad7)") (class "Default")
      (node (ref "M1") (pin "7") (pinfunction "P1.14_7") (pintype "passive+no_connect"))
    )
    (net (code "73") (name "unconnected-(M1-P1.15-Pad8)") (class "Default")
      (node (ref "M1") (pin "8") (pinfunction "P1.15_8") (pintype "passive+no_connect"))
    )
    (net (code "74") (name "unconnected-(M1-VBUS-Pad32)") (class "Default")
      (node (ref "M1") (pin "32") (pinfunction "VBUS_32") (pintype "passive+no_connect"))
    )
    (net (code "75") (name "unconnected-(P3-Pad1)") (class "Default")
      (node (ref "P3") (pin "1") (pinfunction "1_1") (pintype "passive+no_connect"))
    )
    (net (code "76") (name "unconnected-(P3-Pad2)") (class "Default")
      (node (ref "P3") (pin "2") (pinfunction "2_2") (pintype "passive+no_connect"))
    )
    (net (code "77") (name "unconnected-(P3-Pad3)") (class "Default")
      (node (ref "P3") (pin "3") (pinfunction "3_3") (pintype "passive+no_connect"))
    )
    (net (code "78") (name "unconnected-(P3-Pad4)") (class "Default")
      (node (ref "P3") (pin "4") (pinfunction "4_4") (pintype "passive+no_connect"))
    )
    (net (code "79") (name "unconnected-(P3-Pad5)") (class "Default")
      (node (ref "P3") (pin "5") (pinfunction "5_5") (pintype "passive+no_connect"))
    )
    (net (code "80") (name "unconnected-(P3-Pad6)") (class "Default")
      (node (ref "P3") (pin "6") (pinfunction "6_6") (pintype "passive+no_connect"))
    )
    (net (code "81") (name "unconnected-(SW1-Pad2)") (class "Default")
      (node (ref "SW1") (pin "2") (pinfunction "2_2") (pintype "passive+no_connect"))
    )
    (net (code "82") (name "unconnected-(SW1-Pad4)") (class "Default")
      (node (ref "SW1") (pin "4") (pinfunction "4_4") (pintype "passive+no_connect"))
    )
    (net (code "83") (name "unconnected-(U2-ASCX-Pad3)") (class "Default")
      (node (ref "U2") (pin "3") (pinfunction "ASCX_3") (pintype "bidirectional+no_connect"))
    )
    (net (code "84") (name "unconnected-(U2-ASDX-Pad2)") (class "Default")
      (node (ref "U2") (pin "2") (pinfunction "ASDX_2") (pintype "bidirectional+no_connect"))
    )
    (net (code "85") (name "unconnected-(U2-INT2-Pad9)") (class "Default")
      (node (ref "U2") (pin "9") (pinfunction "INT2_9") (pintype "bidirectional+no_connect"))
    )
    (net (code "86") (name "unconnected-(U2-OCSB-Pad10)") (class "Default")
      (node (ref "U2") (pin "10") (pinfunction "OCSB_10") (pintype "input+no_connect"))
    )
    (net (code "87") (name "unconnected-(U2-OSDO-Pad11)") (class "Default")
      (node (ref "U2") (pin "11") (pinfunction "OSDO_11") (pintype "output+no_connect"))
    )
  )
)
